# drv_ps.net
KiCad netlist of a schematic drawn in EAGLE
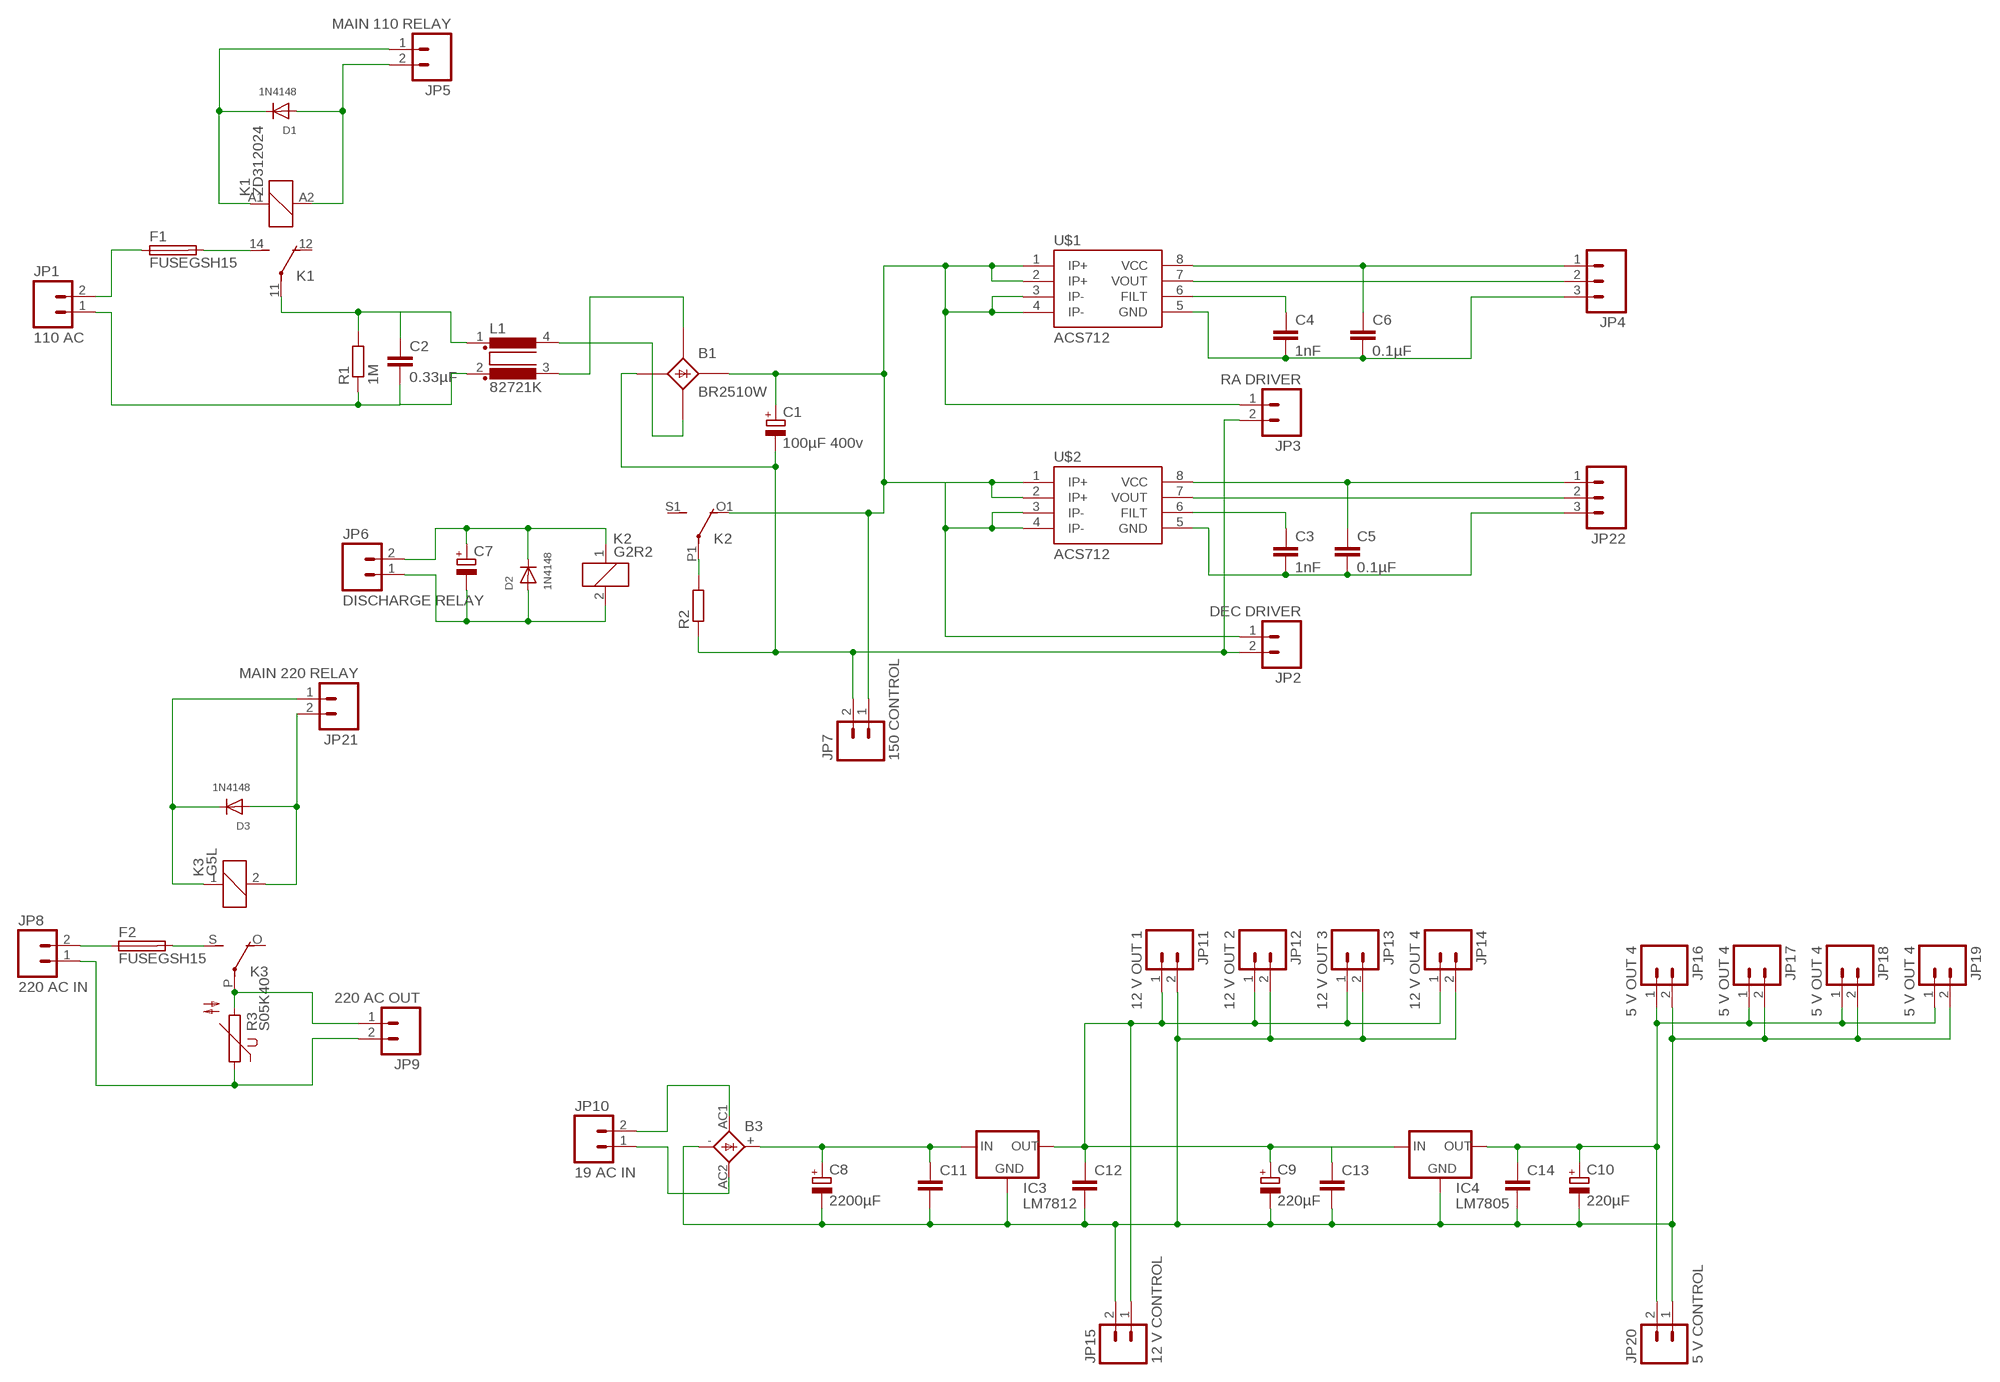
[diagram p0: schematic, sheet 1]

(export (version "E")
  (design (tool "Eeschema 10.0.6"))
  (components
    (comp (ref "B1")
      (value "BR2510W")
      (footprint "eagle-import:B25A-")
      (libsource (lib "eagle-import") (part "B25A-"))
    )
    (comp (ref "B3")
      (value "GBPC1")
      (footprint "eagle-import:GBPC1")
      (libsource (lib "eagle-import") (part "GBPC1"))
    )
    (comp (ref "C1")
      (value "100µF 400v")
      (footprint "eagle-import:EB35D")
      (libsource (lib "eagle-import") (part "CPOL-EUE10-35"))
    )
    (comp (ref "C2")
      (value "0.33µF")
      (footprint "eagle-import:C150-054X183")
      (libsource (lib "eagle-import") (part "C-EU150-054X183"))
    )
    (comp (ref "C3")
      (value "1nF")
      (footprint "eagle-import:C0805")
      (libsource (lib "eagle-import") (part "C-EUC0805"))
    )
    (comp (ref "C4")
      (value "1nF")
      (footprint "eagle-import:C0805")
      (libsource (lib "eagle-import") (part "C-EUC0805"))
    )
    (comp (ref "C5")
      (value "0.1µF")
      (footprint "eagle-import:C0805")
      (libsource (lib "eagle-import") (part "C-EUC0805"))
    )
    (comp (ref "C6")
      (value "0.1µF")
      (footprint "eagle-import:C0805")
      (libsource (lib "eagle-import") (part "C-EUC0805"))
    )
    (comp (ref "C7")
      (value "CPOL-EUE2,5-6E")
      (footprint "eagle-import:E2,5-6E")
      (libsource (lib "eagle-import") (part "resistor_CPOL-EUE2,5-6E"))
    )
    (comp (ref "C8")
      (value "2200µF")
      (footprint "eagle-import:E5-13")
      (libsource (lib "eagle-import") (part "CPOL-EUE5-13"))
    )
    (comp (ref "C9")
      (value "220µF")
      (footprint "eagle-import:E2,5-5")
      (libsource (lib "eagle-import") (part "CPOL-EUE2.5-5"))
    )
    (comp (ref "C10")
      (value "220µF")
      (footprint "eagle-import:E2,5-5")
      (libsource (lib "eagle-import") (part "CPOL-EUE2.5-5"))
    )
    (comp (ref "C11")
      (value "C-EUC0805")
      (footprint "eagle-import:C0805")
      (libsource (lib "eagle-import") (part "C-EUC0805"))
    )
    (comp (ref "C12")
      (value "C-EUC0805")
      (footprint "eagle-import:C0805")
      (libsource (lib "eagle-import") (part "C-EUC0805"))
    )
    (comp (ref "C13")
      (value "C-EUC0805")
      (footprint "eagle-import:C0805")
      (libsource (lib "eagle-import") (part "C-EUC0805"))
    )
    (comp (ref "C14")
      (value "C-EUC0805")
      (footprint "eagle-import:C0805")
      (libsource (lib "eagle-import") (part "C-EUC0805"))
    )
    (comp (ref "D1")
      (value "1N4148")
      (footprint "eagle-import:DO-1N4148")
      (libsource (lib "eagle-import") (part "DIODEDO-1N4148"))
    )
    (comp (ref "D2")
      (value "1N4148")
      (footprint "eagle-import:DO-1N4148")
      (libsource (lib "eagle-import") (part "DIODEDO-1N4148"))
    )
    (comp (ref "D3")
      (value "1N4148")
      (footprint "eagle-import:DO-1N4148")
      (libsource (lib "eagle-import") (part "DIODEDO-1N4148"))
    )
    (comp (ref "F1")
      (value "FUSEGSH15")
      (footprint "eagle-import:GSH15")
      (libsource (lib "eagle-import") (part "FUSEGSH15"))
    )
    (comp (ref "F2")
      (value "FUSEGSH15")
      (footprint "eagle-import:GSH15")
      (libsource (lib "eagle-import") (part "FUSEGSH15"))
    )
    (comp (ref "IC3")
      (value "LM7812")
      (footprint "eagle-import:78XXL")
      (libsource (lib "eagle-import") (part "V_REG_78XXSIDE"))
    )
    (comp (ref "IC4")
      (value "LM7805")
      (footprint "eagle-import:78XXL")
      (libsource (lib "eagle-import") (part "V_REG_78XXSIDE"))
    )
    (comp (ref "JP1")
      (value "110 AC")
      (footprint "eagle-import:SCREWTERMINAL-5MM-2")
      (libsource (lib "eagle-import") (part "M025MM"))
    )
    (comp (ref "JP2")
      (value "DEC DRIVER")
      (footprint "eagle-import:SCREWTERMINAL-5MM-2")
      (libsource (lib "eagle-import") (part "M025MM"))
    )
    (comp (ref "JP3")
      (value "RA DRIVER")
      (footprint "eagle-import:SCREWTERMINAL-5MM-2")
      (libsource (lib "eagle-import") (part "M025MM"))
    )
    (comp (ref "JP4")
      (value "M03POLAR")
      (footprint "eagle-import:MOLEX-1X3")
      (libsource (lib "eagle-import") (part "M03POLAR"))
    )
    (comp (ref "JP5")
      (value "MAIN 110 RELAY")
      (footprint "eagle-import:MOLEX-1X2")
      (libsource (lib "eagle-import") (part "M02POLAR"))
    )
    (comp (ref "JP6")
      (value "DISCHARGE RELAY")
      (footprint "eagle-import:MOLEX-1X2")
      (libsource (lib "eagle-import") (part "M02POLAR"))
    )
    (comp (ref "JP7")
      (value "150 CONTROL")
      (footprint "eagle-import:MOLEX-1X2")
      (libsource (lib "eagle-import") (part "M02POLAR"))
    )
    (comp (ref "JP8")
      (value "220 AC IN")
      (footprint "eagle-import:SCREWTERMINAL-5MM-2")
      (libsource (lib "eagle-import") (part "M025MM"))
    )
    (comp (ref "JP9")
      (value "220 AC OUT")
      (footprint "eagle-import:SCREWTERMINAL-5MM-2")
      (libsource (lib "eagle-import") (part "M025MM"))
    )
    (comp (ref "JP10")
      (value "19 AC IN")
      (footprint "eagle-import:SCREWTERMINAL-5MM-2")
      (libsource (lib "eagle-import") (part "M025MM"))
    )
    (comp (ref "JP11")
      (value "12 V OUT 1")
      (footprint "eagle-import:JST-2-PTH-VERT")
      (libsource (lib "eagle-import") (part "M02JST-PTH-VERT"))
    )
    (comp (ref "JP12")
      (value "12 V OUT 2")
      (footprint "eagle-import:JST-2-PTH-VERT")
      (libsource (lib "eagle-import") (part "M02JST-PTH-VERT"))
    )
    (comp (ref "JP13")
      (value "12 V OUT 3")
      (footprint "eagle-import:JST-2-PTH-VERT")
      (libsource (lib "eagle-import") (part "M02JST-PTH-VERT"))
    )
    (comp (ref "JP14")
      (value "12 V OUT 4")
      (footprint "eagle-import:JST-2-PTH-VERT")
      (libsource (lib "eagle-import") (part "M02JST-PTH-VERT"))
    )
    (comp (ref "JP15")
      (value "12 V CONTROL")
      (footprint "eagle-import:1X02")
      (libsource (lib "eagle-import") (part "M02PTH"))
    )
    (comp (ref "JP16")
      (value "5 V OUT 4")
      (footprint "eagle-import:JST-2-PTH-VERT")
      (libsource (lib "eagle-import") (part "M02JST-PTH-VERT"))
    )
    (comp (ref "JP17")
      (value "5 V OUT 4")
      (footprint "eagle-import:JST-2-PTH-VERT")
      (libsource (lib "eagle-import") (part "M02JST-PTH-VERT"))
    )
    (comp (ref "JP18")
      (value "5 V OUT 4")
      (footprint "eagle-import:JST-2-PTH-VERT")
      (libsource (lib "eagle-import") (part "M02JST-PTH-VERT"))
    )
    (comp (ref "JP19")
      (value "5 V OUT 4")
      (footprint "eagle-import:JST-2-PTH-VERT")
      (libsource (lib "eagle-import") (part "M02JST-PTH-VERT"))
    )
    (comp (ref "JP20")
      (value "5 V CONTROL")
      (footprint "eagle-import:1X02")
      (libsource (lib "eagle-import") (part "M02PTH"))
    )
    (comp (ref "JP21")
      (value "MAIN 220 RELAY")
      (footprint "eagle-import:MOLEX-1X2")
      (libsource (lib "eagle-import") (part "M02POLAR"))
    )
    (comp (ref "JP22")
      (value "M03POLAR")
      (footprint "eagle-import:MOLEX-1X3")
      (libsource (lib "eagle-import") (part "M03POLAR"))
    )
    (comp (ref "K1")
      (value "ZD312024")
      (footprint "eagle-import:ZD1")
      (libsource (lib "eagle-import") (part "ZD?132024"))
    )
    (comp (ref "K2")
      (value "G2R2")
      (footprint "eagle-import:G2R2")
      (fields (field (name "MF") "OMRON COMPONENTS USA") (field (name "MPN") "G2R-2-DC6"))
      (libsource (lib "eagle-import") (part "G2R2"))
    )
    (comp (ref "K3")
      (value "G5L")
      (footprint "eagle-import:G5LE")
      (libsource (lib "eagle-import") (part "G5L"))
    )
    (comp (ref "L1")
      (value "82721K")
      (footprint "eagle-import:82721K")
      (libsource (lib "eagle-import") (part "82721K"))
    )
    (comp (ref "R1")
      (value "1M")
      (footprint "eagle-import:0411_15")
      (libsource (lib "eagle-import") (part "R-EU_0411/15"))
    )
    (comp (ref "R2")
      (value "R-EU_VTA54")
      (footprint "eagle-import:VTA54")
      (libsource (lib "eagle-import") (part "R-EU_VTA54"))
    )
    (comp (ref "R3")
      (value "S05K40")
      (footprint "eagle-import:S05K40")
      (libsource (lib "eagle-import") (part "S05K40"))
    )
    (comp (ref "U$1")
      (value "ACS712")
      (footprint "eagle-import:SO08")
      (libsource (lib "eagle-import") (part "ACS712"))
    )
    (comp (ref "U$2")
      (value "ACS712")
      (footprint "eagle-import:SO08")
      (libsource (lib "eagle-import") (part "ACS712"))
    )
  )
  (nets
    (net (code "1") (name "Net-(B1---Pad-1)") (class "Default")
      (node (ref "B1") (pin "-1") (pinfunction "-_-1") (pintype "passive"))
      (node (ref "C1") (pin "-") (pinfunction "-_-") (pintype "passive"))
      (node (ref "JP2") (pin "2") (pinfunction "2_2") (pintype "passive"))
      (node (ref "JP3") (pin "2") (pinfunction "2_2") (pintype "passive"))
      (node (ref "JP7") (pin "2") (pinfunction "2_2") (pintype "passive"))
      (node (ref "R2") (pin "1") (pinfunction "1_1") (pintype "passive"))
    )
    (net (code "2") (name "Net-(B3-Pad+)") (class "Default")
      (node (ref "B3") (pin "+") (pinfunction "+_+") (pintype "passive"))
      (node (ref "C11") (pin "1") (pinfunction "1_1") (pintype "passive"))
      (node (ref "C8") (pin "+") (pinfunction "+_+") (pintype "passive"))
      (node (ref "IC3") (pin "IN") (pinfunction "IN_IN") (pintype "input"))
    )
    (net (code "3") (name "Net-(B3-Pad-)") (class "Default")
      (node (ref "B3") (pin "-") (pinfunction "-_-") (pintype "passive"))
      (node (ref "C10") (pin "-") (pinfunction "-_-") (pintype "passive"))
      (node (ref "C11") (pin "2") (pinfunction "2_2") (pintype "passive"))
      (node (ref "C12") (pin "2") (pinfunction "2_2") (pintype "passive"))
      (node (ref "C13") (pin "2") (pinfunction "2_2") (pintype "passive"))
      (node (ref "C14") (pin "2") (pinfunction "2_2") (pintype "passive"))
      (node (ref "C8") (pin "-") (pinfunction "-_-") (pintype "passive"))
      (node (ref "C9") (pin "-") (pinfunction "-_-") (pintype "passive"))
      (node (ref "IC3") (pin "GND") (pinfunction "GND_GND") (pintype "input"))
      (node (ref "IC4") (pin "GND") (pinfunction "GND_GND") (pintype "input"))
      (node (ref "JP11") (pin "2") (pinfunction "2_2") (pintype "passive"))
      (node (ref "JP12") (pin "2") (pinfunction "2_2") (pintype "passive"))
      (node (ref "JP13") (pin "2") (pinfunction "2_2") (pintype "passive"))
      (node (ref "JP14") (pin "2") (pinfunction "2_2") (pintype "passive"))
      (node (ref "JP15") (pin "2") (pinfunction "2_2") (pintype "passive"))
      (node (ref "JP16") (pin "2") (pinfunction "2_2") (pintype "passive"))
      (node (ref "JP17") (pin "2") (pinfunction "2_2") (pintype "passive"))
      (node (ref "JP18") (pin "2") (pinfunction "2_2") (pintype "passive"))
      (node (ref "JP19") (pin "2") (pinfunction "2_2") (pintype "passive"))
      (node (ref "JP20") (pin "1") (pinfunction "1_1") (pintype "passive"))
    )
    (net (code "4") (name "Net-(B3-PadAC1)") (class "Default")
      (node (ref "B3") (pin "AC1") (pinfunction "AC1_AC1") (pintype "passive"))
      (node (ref "JP10") (pin "2") (pinfunction "2_2") (pintype "passive"))
    )
    (net (code "5") (name "Net-(B3-PadAC2)") (class "Default")
      (node (ref "B3") (pin "AC2") (pinfunction "AC2_AC2") (pintype "passive"))
      (node (ref "JP10") (pin "1") (pinfunction "1_1") (pintype "passive"))
    )
    (net (code "6") (name "Net-(C7-Pad+)") (class "Default")
      (node (ref "C7") (pin "+") (pinfunction "+_+") (pintype "passive"))
      (node (ref "D2") (pin "C") (pinfunction "C_C") (pintype "passive"))
      (node (ref "JP6") (pin "2") (pinfunction "2_2") (pintype "passive"))
      (node (ref "K2") (pin "1") (pinfunction "1_1") (pintype "passive"))
    )
    (net (code "7") (name "Net-(C7-Pad-)") (class "Default")
      (node (ref "C7") (pin "-") (pinfunction "-_-") (pintype "passive"))
      (node (ref "D2") (pin "A") (pinfunction "A_A") (pintype "passive"))
      (node (ref "JP6") (pin "1") (pinfunction "1_1") (pintype "passive"))
      (node (ref "K2") (pin "2") (pinfunction "2_2") (pintype "passive"))
    )
    (net (code "8") (name "Net-(C10-Pad+)") (class "Default")
      (node (ref "C10") (pin "+") (pinfunction "+_+") (pintype "passive"))
      (node (ref "C14") (pin "1") (pinfunction "1_1") (pintype "passive"))
      (node (ref "IC4") (pin "OUT") (pinfunction "OUT_OUT") (pintype "output"))
      (node (ref "JP16") (pin "1") (pinfunction "1_1") (pintype "passive"))
      (node (ref "JP17") (pin "1") (pinfunction "1_1") (pintype "passive"))
      (node (ref "JP18") (pin "1") (pinfunction "1_1") (pintype "passive"))
      (node (ref "JP19") (pin "1") (pinfunction "1_1") (pintype "passive"))
      (node (ref "JP20") (pin "2") (pinfunction "2_2") (pintype "passive"))
    )
    (net (code "9") (name "Net-(C12-Pad1)") (class "Default")
      (node (ref "C12") (pin "1") (pinfunction "1_1") (pintype "passive"))
      (node (ref "C13") (pin "1") (pinfunction "1_1") (pintype "passive"))
      (node (ref "C9") (pin "+") (pinfunction "+_+") (pintype "passive"))
      (node (ref "IC3") (pin "OUT") (pinfunction "OUT_OUT") (pintype "output"))
      (node (ref "IC4") (pin "IN") (pinfunction "IN_IN") (pintype "input"))
      (node (ref "JP11") (pin "1") (pinfunction "1_1") (pintype "passive"))
      (node (ref "JP12") (pin "1") (pinfunction "1_1") (pintype "passive"))
      (node (ref "JP13") (pin "1") (pinfunction "1_1") (pintype "passive"))
      (node (ref "JP14") (pin "1") (pinfunction "1_1") (pintype "passive"))
      (node (ref "JP15") (pin "1") (pinfunction "1_1") (pintype "passive"))
    )
    (net (code "10") (name "Net-(D3-PadA)") (class "Default")
      (node (ref "D3") (pin "A") (pinfunction "A_A") (pintype "passive"))
      (node (ref "JP21") (pin "2") (pinfunction "2_2") (pintype "passive"))
      (node (ref "K3") (pin "2") (pinfunction "2_2") (pintype "passive"))
    )
    (net (code "11") (name "Net-(D3-PadC)") (class "Default")
      (node (ref "D3") (pin "C") (pinfunction "C_C") (pintype "passive"))
      (node (ref "JP21") (pin "1") (pinfunction "1_1") (pintype "passive"))
      (node (ref "K3") (pin "1") (pinfunction "1_1") (pintype "passive"))
    )
    (net (code "12") (name "Net-(F1-Pad1)") (class "Default")
      (node (ref "F1") (pin "1") (pinfunction "1_1") (pintype "passive"))
      (node (ref "JP1") (pin "2") (pinfunction "2_2") (pintype "passive"))
    )
    (net (code "13") (name "Net-(F2-Pad1)") (class "Default")
      (node (ref "F2") (pin "1") (pinfunction "1_1") (pintype "passive"))
      (node (ref "JP8") (pin "2") (pinfunction "2_2") (pintype "passive"))
    )
    (net (code "14") (name "Net-(F2-Pad2)") (class "Default")
      (node (ref "F2") (pin "2") (pinfunction "2_2") (pintype "passive"))
      (node (ref "K3") (pin "S") (pinfunction "S_S") (pintype "passive"))
    )
    (net (code "15") (name "Net-(JP8-Pad1)") (class "Default")
      (node (ref "JP8") (pin "1") (pinfunction "1_1") (pintype "passive"))
      (node (ref "JP9") (pin "2") (pinfunction "2_2") (pintype "passive"))
      (node (ref "R3") (pin "1") (pinfunction "1_1") (pintype "passive"))
    )
    (net (code "16") (name "Net-(JP9-Pad1)") (class "Default")
      (node (ref "JP9") (pin "1") (pinfunction "1_1") (pintype "passive"))
      (node (ref "K3") (pin "P") (pinfunction "P_P") (pintype "passive"))
      (node (ref "R3") (pin "2") (pinfunction "2_2") (pintype "passive"))
    )
    (net (code "17") (name "Net-(K1A-1)") (class "Default")
      (node (ref "D1") (pin "C") (pinfunction "C_C") (pintype "passive"))
      (node (ref "JP5") (pin "1") (pinfunction "1_1") (pintype "passive"))
      (node (ref "K1") (pin "A1") (pinfunction "1_A1") (pintype "passive"))
    )
    (net (code "18") (name "Net-(K1A-2)") (class "Default")
      (node (ref "D1") (pin "A") (pinfunction "A_A") (pintype "passive"))
      (node (ref "JP5") (pin "2") (pinfunction "2_2") (pintype "passive"))
      (node (ref "K1") (pin "A2") (pinfunction "2_A2") (pintype "passive"))
    )
    (net (code "19") (name "Net-(K1B-P)") (class "Default")
      (node (ref "C2") (pin "1") (pinfunction "1_1") (pintype "passive"))
      (node (ref "K1") (pin "11") (pinfunction "P_11") (pintype "passive"))
      (node (ref "L1") (pin "1") (pinfunction "1_1") (pintype "passive"))
      (node (ref "R1") (pin "2") (pinfunction "2_2") (pintype "passive"))
    )
    (net (code "20") (name "Net-(K1B-S)") (class "Default")
      (node (ref "F1") (pin "2") (pinfunction "2_2") (pintype "passive"))
      (node (ref "K1") (pin "14") (pinfunction "S_14") (pintype "passive"))
    )
    (net (code "21") (name "Net-(K2B-O)") (class "Default")
      (node (ref "B1") (pin "+1") (pinfunction "+_+1") (pintype "passive"))
      (node (ref "C1") (pin "+") (pinfunction "+_+") (pintype "passive"))
      (node (ref "JP2") (pin "1") (pinfunction "1_1") (pintype "passive"))
      (node (ref "JP3") (pin "1") (pinfunction "1_1") (pintype "passive"))
      (node (ref "JP7") (pin "1") (pinfunction "1_1") (pintype "passive"))
      (node (ref "K2") (pin "O1") (pinfunction "O_O1") (pintype "passive"))
      (node (ref "U$1") (pin "1") (pinfunction "IP+_1") (pintype "bidirectional"))
      (node (ref "U$1") (pin "2") (pinfunction "IP+_2") (pintype "bidirectional"))
      (node (ref "U$1") (pin "3") (pinfunction "IP-_3") (pintype "bidirectional"))
      (node (ref "U$1") (pin "4") (pinfunction "IP-_4") (pintype "bidirectional"))
      (node (ref "U$2") (pin "1") (pinfunction "IP+_1") (pintype "bidirectional"))
      (node (ref "U$2") (pin "2") (pinfunction "IP+_2") (pintype "bidirectional"))
      (node (ref "U$2") (pin "3") (pinfunction "IP-_3") (pintype "bidirectional"))
      (node (ref "U$2") (pin "4") (pinfunction "IP-_4") (pintype "bidirectional"))
    )
    (net (code "22") (name "Net-(K2B-P)") (class "Default")
      (node (ref "K2") (pin "P1") (pinfunction "P_P1") (pintype "passive"))
      (node (ref "R2") (pin "2") (pinfunction "2_2") (pintype "passive"))
    )
    (net (code "23") (name "Net-(L1-2)") (class "Default")
      (node (ref "B1") (pin "AC2-") (pinfunction "AC2_AC2-") (pintype "passive"))
      (node (ref "L1") (pin "4") (pinfunction "2_4") (pintype "passive"))
    )
    (net (code "24") (name "Net-(L1-3)") (class "Default")
      (node (ref "C2") (pin "2") (pinfunction "2_2") (pintype "passive"))
      (node (ref "JP1") (pin "1") (pinfunction "1_1") (pintype "passive"))
      (node (ref "L1") (pin "2") (pinfunction "3_2") (pintype "passive"))
      (node (ref "R1") (pin "1") (pinfunction "1_1") (pintype "passive"))
    )
    (net (code "25") (name "Net-(L1-4)") (class "Default")
      (node (ref "B1") (pin "AC1-") (pinfunction "AC1_AC1-") (pintype "passive"))
      (node (ref "L1") (pin "3") (pinfunction "4_3") (pintype "passive"))
    )
    (net (code "26") (name "Net-(U$1-FILT)") (class "Default")
      (node (ref "C4") (pin "1") (pinfunction "1_1") (pintype "passive"))
      (node (ref "U$1") (pin "6") (pinfunction "FILT_6") (pintype "bidirectional"))
    )
    (net (code "27") (name "Net-(U$1-GND)") (class "Default")
      (node (ref "C4") (pin "2") (pinfunction "2_2") (pintype "passive"))
      (node (ref "C6") (pin "2") (pinfunction "2_2") (pintype "passive"))
      (node (ref "JP4") (pin "3") (pinfunction "3_3") (pintype "passive"))
      (node (ref "U$1") (pin "5") (pinfunction "GND_5") (pintype "bidirectional"))
    )
    (net (code "28") (name "Net-(U$1-VCC)") (class "Default")
      (node (ref "C6") (pin "1") (pinfunction "1_1") (pintype "passive"))
      (node (ref "JP4") (pin "1") (pinfunction "1_1") (pintype "passive"))
      (node (ref "U$1") (pin "8") (pinfunction "VCC_8") (pintype "bidirectional"))
    )
    (net (code "29") (name "Net-(U$1-VOUT)") (class "Default")
      (node (ref "JP4") (pin "2") (pinfunction "2_2") (pintype "passive"))
      (node (ref "U$1") (pin "7") (pinfunction "VOUT_7") (pintype "bidirectional"))
    )
    (net (code "30") (name "Net-(U$2-FILT)") (class "Default")
      (node (ref "C3") (pin "1") (pinfunction "1_1") (pintype "passive"))
      (node (ref "U$2") (pin "6") (pinfunction "FILT_6") (pintype "bidirectional"))
    )
    (net (code "31") (name "Net-(U$2-GND)") (class "Default")
      (node (ref "C3") (pin "2") (pinfunction "2_2") (pintype "passive"))
      (node (ref "C5") (pin "2") (pinfunction "2_2") (pintype "passive"))
      (node (ref "JP22") (pin "3") (pinfunction "3_3") (pintype "passive"))
      (node (ref "U$2") (pin "5") (pinfunction "GND_5") (pintype "bidirectional"))
    )
    (net (code "32") (name "Net-(U$2-VCC)") (class "Default")
      (node (ref "C5") (pin "1") (pinfunction "1_1") (pintype "passive"))
      (node (ref "JP22") (pin "1") (pinfunction "1_1") (pintype "passive"))
      (node (ref "U$2") (pin "8") (pinfunction "VCC_8") (pintype "bidirectional"))
    )
    (net (code "33") (name "Net-(U$2-VOUT)") (class "Default")
      (node (ref "JP22") (pin "2") (pinfunction "2_2") (pintype "passive"))
      (node (ref "U$2") (pin "7") (pinfunction "VOUT_7") (pintype "bidirectional"))
    )
    (net (code "34") (name "unconnected-(B1-Pad+)") (class "Default")
      (node (ref "B1") (pin "+") (pinfunction "+_+") (pintype "passive"))
    )
    (net (code "35") (name "unconnected-(B1-Pad-)") (class "Default")
      (node (ref "B1") (pin "-") (pinfunction "-_-") (pintype "passive"))
    )
    (net (code "36") (name "unconnected-(B1-PadAC1)") (class "Default")
      (node (ref "B1") (pin "AC1") (pinfunction "AC1_AC1") (pintype "passive"))
    )
    (net (code "37") (name "unconnected-(B1-PadAC2)") (class "Default")
      (node (ref "B1") (pin "AC2") (pinfunction "AC2_AC2") (pintype "passive"))
    )
    (net (code "38") (name "unconnected-(K1B-O-Pad12)") (class "Default")
      (node (ref "K1") (pin "12") (pinfunction "O_12") (pintype "passive"))
    )
    (net (code "39") (name "unconnected-(K2B-S-PadS1)") (class "Default")
      (node (ref "K2") (pin "S1") (pinfunction "S_S1") (pintype "passive"))
    )
    (net (code "40") (name "unconnected-(K3-PadO)") (class "Default")
      (node (ref "K3") (pin "O") (pinfunction "O_O") (pintype "passive"))
    )
  )
)
